# Filtr2.net
KiCad netlist of a schematic drawn in Altium Designer
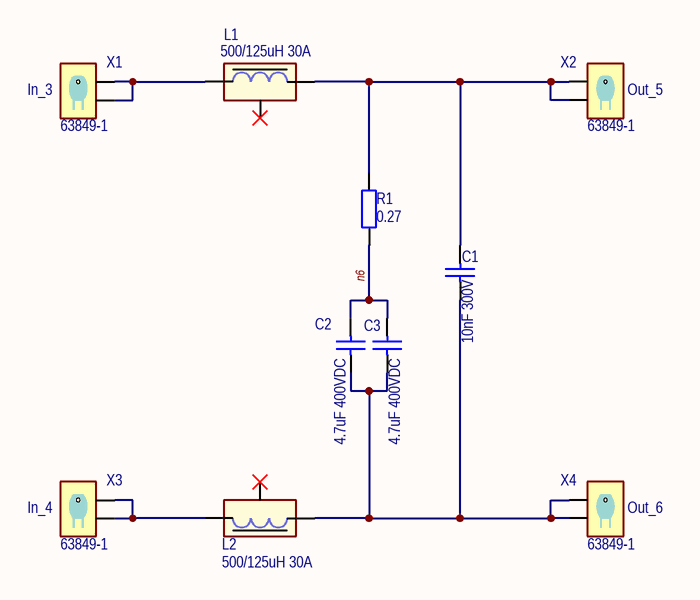
[diagram p0: Filtr2.SchDoc]

(export (version "E")
  (design (tool "Eeschema 10.0.6"))
  (components
    (comp (ref "C1")
      (value "10nF 300V")
      (footprint "mainLib:C Y2 D13 7.5b")
      (description "Ceramic D=14 LS=7.5 300VAC X1Y2")
      (fields (field (name "PARTNUMBER") "DE2F3KY103MA3") (field (name "MANUFACTURER") "Murata"))
      (libsource (lib "mainRCLib") (part "C X1Y2 10nF D13 LS7.5"))
    )
    (comp (ref "C2")
      (value "4.7uF 400VDC")
      (footprint "mainLib:MKP_W20_H39.5_L41.5_LS37.5")
      (description "Polypropelene W20 H39.5 L41.5 LS37.5 400VDC 10%")
      (fields (field (name "PARTNUMBER") "MKP1G044707G00K") (field (name "MANUFACTURER") "Wima"))
      (libsource (lib "mainRCLib") (part "MKP1 4.7uF 10% 400VDC"))
    )
    (comp (ref "C3")
      (value "4.7uF 400VDC")
      (footprint "mainLib:MKP_W20_H39.5_L41.5_LS37.5")
      (description "Polypropelene W20 H39.5 L41.5 LS37.5 400VDC 10%")
      (fields (field (name "PARTNUMBER") "MKP1G044707G00K") (field (name "MANUFACTURER") "Wima"))
      (libsource (lib "mainRCLib") (part "MKP1 4.7uF 10% 400VDC"))
    )
    (comp (ref "L1")
      (value "500/125uH 30A")
      (footprint "mainLib:Dross (500/125 uH 30 A)AMAK.671111.034")
      (description "500/125uH 30A  (Core T250-52 X1)")
      (fields (field (name "MANUFACTURER") "OLTEST") (field (name "PARTNUMBER") "АМАК.671111.034"))
      (libsource (lib "") (part "Dross 500/125uH 30A АМАК.671111.034_1"))
    )
    (comp (ref "L2")
      (value "500/125uH 30A")
      (footprint "mainLib:Dross (500/125 uH 30 A)AMAK.671111.034")
      (description "500/125uH 30A  (Core T250-52 X1)")
      (fields (field (name "MANUFACTURER") "OLTEST") (field (name "PARTNUMBER") "АМАК.671111.034"))
      (libsource (lib "mainLib") (part "Dross 500/125uH 30A АМАК.671111.034"))
    )
    (comp (ref "R1")
      (value "0.27")
      (footprint "mainLib:PRW 5W 1050")
      (description "Выводной PRW 5W 0R27 +-5%")
      (fields (field (name "PARTNUMBER") "PRW05WJW27K") (field (name "MANUFACTURER") "RoyalOhm"))
      (libsource (lib "mainRCLib") (part "PRW 0.27 5W +-5%"))
    )
    (comp (ref "X1")
      (value "63849-1")
      (footprint "63849-1+insulator(154719-1)")
      (description "PCB, 6.3х0.8, hole")
      (fields (field (name "MANUFACTURER") "TE Connectivity"))
      (libsource (lib "") (part "63849-1_1"))
    )
    (comp (ref "X2")
      (value "63849-1")
      (footprint "63849-1+insulator(154719-1)")
      (description "PCB, 6.3х0.8, hole")
      (fields (field (name "MANUFACTURER") "TE Connectivity"))
      (libsource (lib "mainLib") (part "63849-1"))
    )
    (comp (ref "X3")
      (value "63849-1")
      (footprint "63849-1+insulator(154719-1)")
      (description "PCB, 6.3х0.8, hole")
      (fields (field (name "MANUFACTURER") "TE Connectivity"))
      (libsource (lib "") (part "63849-1_1"))
    )
    (comp (ref "X4")
      (value "63849-1")
      (footprint "63849-1+insulator(154719-1)")
      (description "PCB, 6.3х0.8, hole")
      (fields (field (name "MANUFACTURER") "TE Connectivity"))
      (libsource (lib "mainLib") (part "63849-1"))
    )
  )
  (nets
    (net (code "1") (name "/n6") (class "Default")
      (node (ref "C2") (pin "2") (pinfunction "2_2") (pintype "passive"))
      (node (ref "C3") (pin "2") (pinfunction "2_2") (pintype "passive"))
      (node (ref "R1") (pin "1") (pinfunction "1_1") (pintype "passive"))
    )
    (net (code "2") (name "Net-(C1-Pad1)") (class "Default")
      (node (ref "C1") (pin "1") (pinfunction "1_1") (pintype "passive"))
      (node (ref "C2") (pin "1") (pinfunction "1_1") (pintype "passive"))
      (node (ref "C3") (pin "1") (pinfunction "1_1") (pintype "passive"))
      (node (ref "L2") (pin "1") (pinfunction "1_1") (pintype "passive"))
      (node (ref "X4") (pin "1") (pinfunction "1_1") (pintype "passive"))
      (node (ref "X4") (pin "2") (pinfunction "2_2") (pintype "passive"))
    )
    (net (code "3") (name "Net-(C1-Pad2)") (class "Default")
      (node (ref "C1") (pin "2") (pinfunction "2_2") (pintype "passive"))
      (node (ref "L1") (pin "2") (pinfunction "2_2") (pintype "passive"))
      (node (ref "R1") (pin "2") (pinfunction "2_2") (pintype "passive"))
      (node (ref "X2") (pin "1") (pinfunction "1_1") (pintype "passive"))
      (node (ref "X2") (pin "2") (pinfunction "2_2") (pintype "passive"))
    )
    (net (code "4") (name "Net-(L1-Pad1)") (class "Default")
      (node (ref "L1") (pin "1") (pinfunction "1_1") (pintype "passive"))
      (node (ref "X1") (pin "1") (pinfunction "1_1") (pintype "passive"))
      (node (ref "X1") (pin "2") (pinfunction "2_2") (pintype "passive"))
    )
    (net (code "5") (name "Net-(L2-Pad2)") (class "Default")
      (node (ref "L2") (pin "2") (pinfunction "2_2") (pintype "passive"))
      (node (ref "X3") (pin "1") (pinfunction "1_1") (pintype "passive"))
      (node (ref "X3") (pin "2") (pinfunction "2_2") (pintype "passive"))
    )
    (net (code "6") (name "unconnected-(L1-Pad3)") (class "Default")
      (node (ref "L1") (pin "3") (pinfunction "3_3") (pintype "passive+no_connect"))
    )
    (net (code "7") (name "unconnected-(L2-Pad3)") (class "Default")
      (node (ref "L2") (pin "3") (pinfunction "3_3") (pintype "passive+no_connect"))
    )
  )
)
